# Environment-ArduinoNano44-Mini-Enclosure.net
KiCad netlist of a schematic drawn in EAGLE
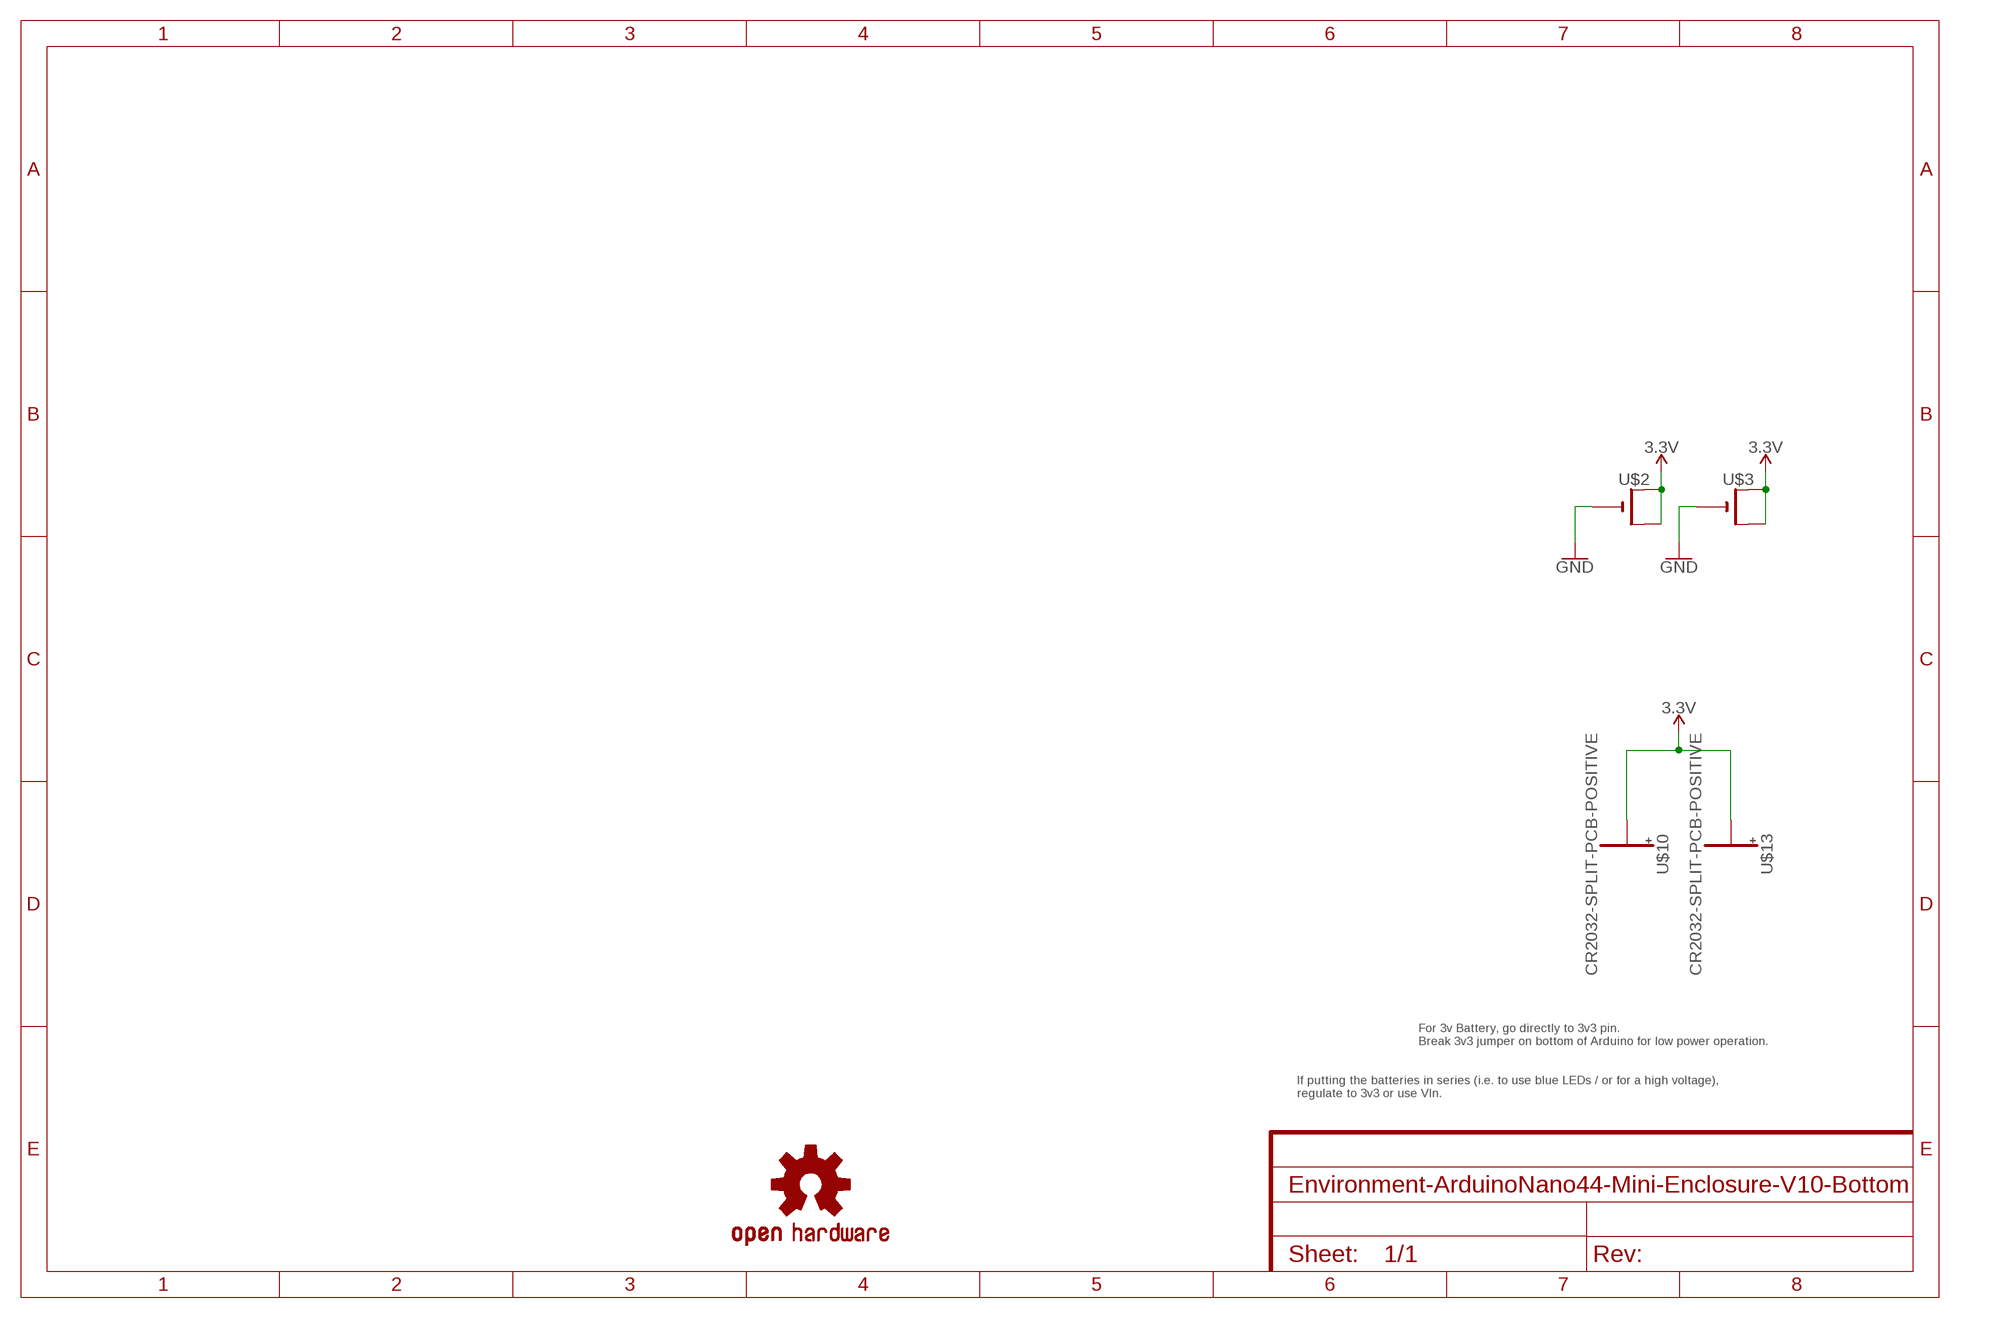
[diagram p0: schematic, sheet 1]

(export (version "E")
  (design (tool "Eeschema 10.0.6"))
  (components
    (comp (ref "LOGO3")
      (value "OSHW-LOGOL")
      (footprint "eagle-import:OSHW-LOGO-L")
      (libsource (lib "eagle-import") (part "OSHW-LOGOL"))
    )
    (comp (ref "U$2")
      (value "CR2032SMT")
      (footprint "eagle-import:CR2032-SMD")
      (libsource (lib "eagle-import") (part "CR2032SMT"))
    )
    (comp (ref "U$3")
      (value "CR2032SMT")
      (footprint "eagle-import:CR2032-SMD")
      (libsource (lib "eagle-import") (part "CR2032SMT"))
    )
    (comp (ref "U$10")
      (value "CR2032-SPLIT-PCB-POSITIVE")
      (footprint "eagle-import:CR2032-SMD-POSITIVE-TERMINAL")
      (libsource (lib "eagle-import") (part "CR2032-SPLIT-PCB-POSITIVE"))
    )
    (comp (ref "U$13")
      (value "CR2032-SPLIT-PCB-POSITIVE")
      (footprint "eagle-import:CR2032-SMD-POSITIVE-TERMINAL")
      (libsource (lib "eagle-import") (part "CR2032-SPLIT-PCB-POSITIVE"))
    )
  )
  (nets
    (net (code "1") (name "3.3V") (class "Default")
      (node (ref "U$10") (pin "+") (pinfunction "+_+") (pintype "power_in"))
      (node (ref "U$13") (pin "+") (pinfunction "+_+") (pintype "power_in"))
      (node (ref "U$2") (pin "+$1") (pinfunction "+_+$1") (pintype "passive"))
      (node (ref "U$2") (pin "+$2") (pinfunction "+1_+$2") (pintype "passive"))
      (node (ref "U$3") (pin "+$1") (pinfunction "+_+$1") (pintype "passive"))
      (node (ref "U$3") (pin "+$2") (pinfunction "+1_+$2") (pintype "passive"))
    )
    (net (code "2") (name "GND") (class "Default")
      (node (ref "U$2") (pin "-") (pinfunction "-_-") (pintype "passive"))
      (node (ref "U$3") (pin "-") (pinfunction "-_-") (pintype "passive"))
    )
  )
)
